# 23_LMS2_RX1_BB_ADC.net
KiCad netlist of a schematic drawn in Altium Designer
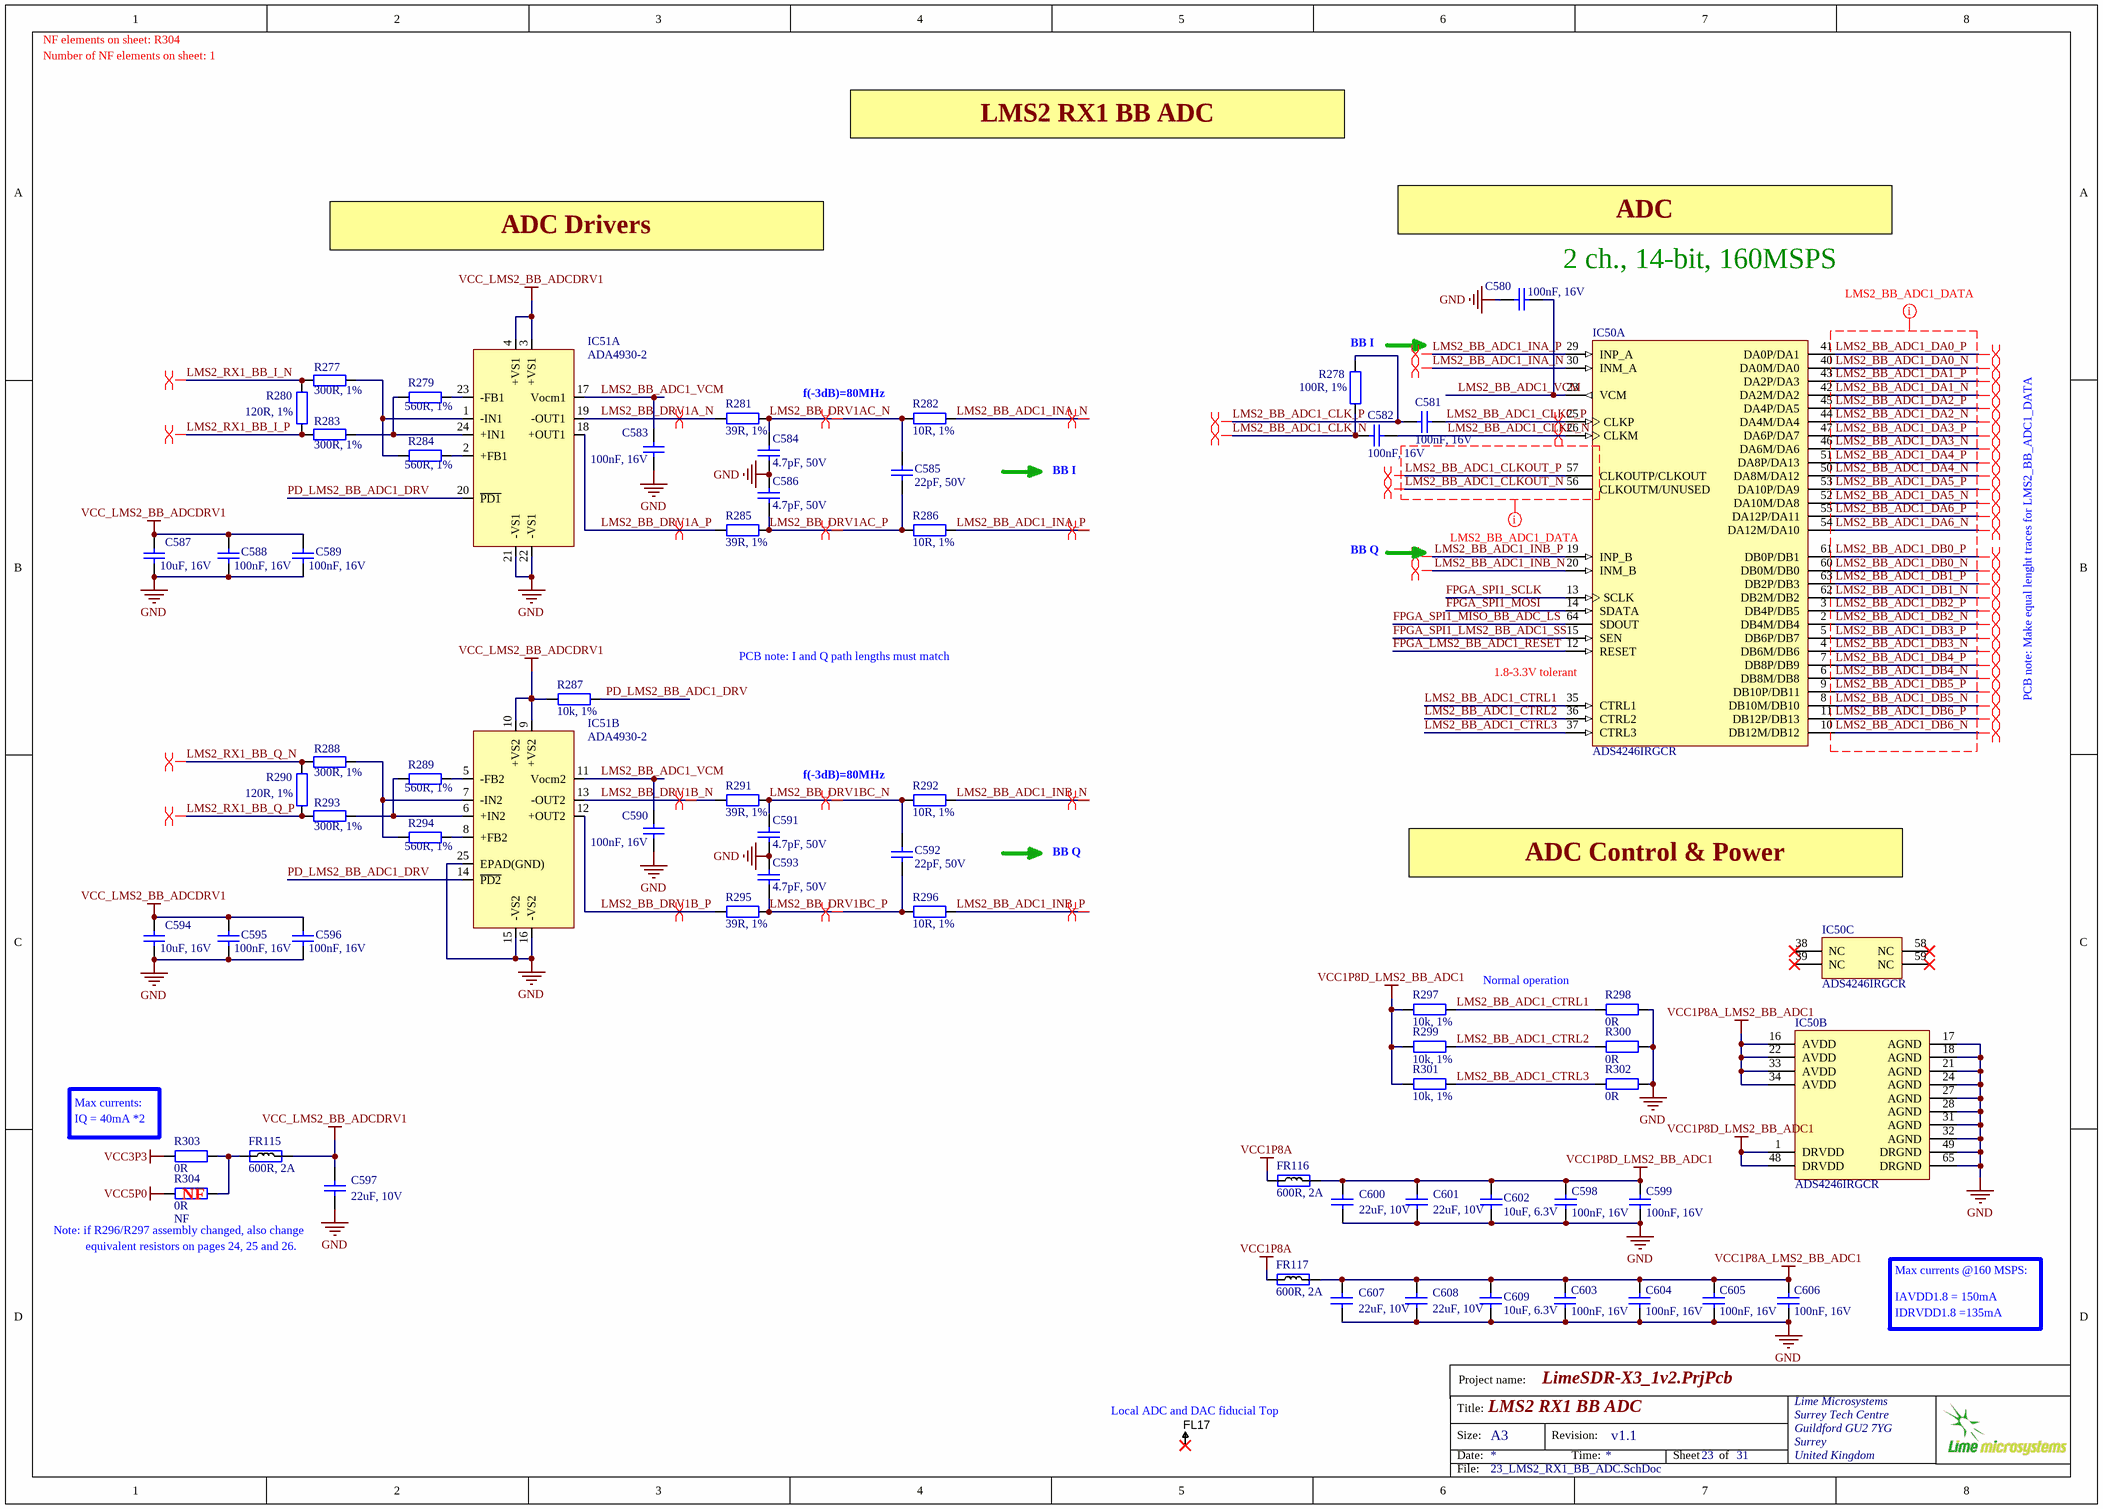
[diagram p0: 23_LMS2_RX1_BB_ADC.SchDoc]

(export (version "E")
  (design (tool "Eeschema 10.0.6"))
  (components
    (comp (ref "C580")
      (value "100nF, 16V")
      (footprint "CAP0402")
      (fields (field (name "TOLERANCE") "10 %") (field (name "MANUFACTURER") "Murata Electronics"))
      (libsource (lib "") (part "Cap_0603_2"))
    )
    (comp (ref "C581")
      (value "100nF, 16V")
      (footprint "CAP0402")
      (fields (field (name "TOLERANCE") "10 %") (field (name "MANUFACTURER") "Murata Electronics"))
      (libsource (lib "") (part "Cap_0603_2"))
    )
    (comp (ref "C582")
      (value "100nF, 16V")
      (footprint "CAP0402")
      (fields (field (name "TOLERANCE") "10 %") (field (name "MANUFACTURER") "Murata Electronics"))
      (libsource (lib "") (part "Cap_0603_5"))
    )
    (comp (ref "C583")
      (value "100nF, 16V")
      (footprint "CAP0402")
      (fields (field (name "TOLERANCE") "10 %") (field (name "MANUFACTURER") "Murata Electronics"))
      (libsource (lib "") (part "Cap_0603_5"))
    )
    (comp (ref "C584")
      (value "4.7pF, 50V")
      (footprint "CAP0402")
      (fields (field (name "MANUFACTURER") "MURATA"))
      (libsource (lib "LimeMicroAltiumLib_schLib") (part "Cap_0402"))
    )
    (comp (ref "C585")
      (value "22pF, 50V")
      (footprint "CAP0402")
      (fields (field (name "TOLERANCE") "±5%") (field (name "MANUFACTURER") "Yageo"))
      (libsource (lib "") (part "Cap_0402_1"))
    )
    (comp (ref "C586")
      (value "4.7pF, 50V")
      (footprint "CAP0402")
      (fields (field (name "MANUFACTURER") "MURATA"))
      (libsource (lib "LimeMicroAltiumLib_schLib") (part "Cap_0402"))
    )
    (comp (ref "C587")
      (value "10uF, 16V")
      (footprint "CAP0603")
      (fields (field (name "MANUFACTURER") "Yageo") (field (name "TOLERANCE") "±20%"))
      (libsource (lib "LimeMicroAltiumLib_schLib") (part "Cap_0603"))
    )
    (comp (ref "C588")
      (value "100nF, 16V")
      (footprint "CAP0402")
      (fields (field (name "TOLERANCE") "10 %") (field (name "MANUFACTURER") "Murata Electronics"))
      (libsource (lib "") (part "Cap_0603_5"))
    )
    (comp (ref "C589")
      (value "100nF, 16V")
      (footprint "CAP0402")
      (fields (field (name "TOLERANCE") "10 %") (field (name "MANUFACTURER") "Murata Electronics"))
      (libsource (lib "") (part "Cap_0603_5"))
    )
    (comp (ref "C590")
      (value "100nF, 16V")
      (footprint "CAP0402")
      (fields (field (name "TOLERANCE") "10 %") (field (name "MANUFACTURER") "Murata Electronics"))
      (libsource (lib "") (part "Cap_0603_7"))
    )
    (comp (ref "C591")
      (value "4.7pF, 50V")
      (footprint "CAP0402")
      (fields (field (name "MANUFACTURER") "MURATA"))
      (libsource (lib "LimeMicroAltiumLib_schLib") (part "Cap_0402"))
    )
    (comp (ref "C592")
      (value "22pF, 50V")
      (footprint "CAP0402")
      (fields (field (name "TOLERANCE") "±5%") (field (name "MANUFACTURER") "Yageo"))
      (libsource (lib "") (part "Cap_0402_1"))
    )
    (comp (ref "C593")
      (value "4.7pF, 50V")
      (footprint "CAP0402")
      (fields (field (name "MANUFACTURER") "MURATA"))
      (libsource (lib "LimeMicroAltiumLib_schLib") (part "Cap_0402"))
    )
    (comp (ref "C594")
      (value "10uF, 16V")
      (footprint "CAP0603")
      (fields (field (name "MANUFACTURER") "Yageo") (field (name "TOLERANCE") "±20%"))
      (libsource (lib "LimeMicroAltiumLib_schLib") (part "Cap_0603"))
    )
    (comp (ref "C595")
      (value "100nF, 16V")
      (footprint "CAP0402")
      (fields (field (name "TOLERANCE") "10 %") (field (name "MANUFACTURER") "Murata Electronics"))
      (libsource (lib "") (part "Cap_0603_5"))
    )
    (comp (ref "C596")
      (value "100nF, 16V")
      (footprint "CAP0402")
      (fields (field (name "TOLERANCE") "10 %") (field (name "MANUFACTURER") "Murata Electronics"))
      (libsource (lib "") (part "Cap_0603_5"))
    )
    (comp (ref "C597")
      (value "22uF, 10V")
      (footprint "CAP0603")
      (fields (field (name "TOLERANCE") "20 %") (field (name "MANUFACTURER") "TDK Corporation"))
      (libsource (lib "") (part "Cap_0603_4"))
    )
    (comp (ref "C598")
      (value "100nF, 16V")
      (footprint "CAP0402")
      (fields (field (name "TOLERANCE") "10 %") (field (name "MANUFACTURER") "Murata Electronics"))
      (libsource (lib "LimeFPGAboard_schLib") (part "Cap_0603"))
    )
    (comp (ref "C599")
      (value "100nF, 16V")
      (footprint "CAP0402")
      (fields (field (name "TOLERANCE") "10 %") (field (name "MANUFACTURER") "Murata Electronics"))
      (libsource (lib "LimeFPGAboard_schLib") (part "Cap_0603"))
    )
    (comp (ref "C600")
      (value "22uF, 10V")
      (footprint "CAP0603")
      (fields (field (name "TOLERANCE") "20 %") (field (name "MANUFACTURER") "TDK Corporation"))
      (libsource (lib "LimeFPGAboard_schLib") (part "Cap_0603"))
    )
    (comp (ref "C601")
      (value "22uF, 10V")
      (footprint "CAP0603")
      (fields (field (name "TOLERANCE") "20 %") (field (name "MANUFACTURER") "TDK Corporation"))
      (libsource (lib "LimeFPGAboard_schLib") (part "Cap_0603"))
    )
    (comp (ref "C602")
      (value "10uF, 6.3V")
      (footprint "CAP0603")
      (fields (field (name "TOLERANCE") "±20%") (field (name "MANUFACTURER") "Yageo"))
      (libsource (lib "") (part "Cap_0603_6"))
    )
    (comp (ref "C603")
      (value "100nF, 16V")
      (footprint "CAP0402")
      (fields (field (name "TOLERANCE") "10 %") (field (name "MANUFACTURER") "Murata Electronics"))
      (libsource (lib "") (part "Cap_0603_3"))
    )
    (comp (ref "C604")
      (value "100nF, 16V")
      (footprint "CAP0402")
      (fields (field (name "TOLERANCE") "10 %") (field (name "MANUFACTURER") "Murata Electronics"))
      (libsource (lib "") (part "Cap_0603_3"))
    )
    (comp (ref "C605")
      (value "100nF, 16V")
      (footprint "CAP0402")
      (fields (field (name "TOLERANCE") "10 %") (field (name "MANUFACTURER") "Murata Electronics"))
      (libsource (lib "") (part "Cap_0603_3"))
    )
    (comp (ref "C606")
      (value "100nF, 16V")
      (footprint "CAP0402")
      (fields (field (name "TOLERANCE") "10 %") (field (name "MANUFACTURER") "Murata Electronics"))
      (libsource (lib "") (part "Cap_0603_3"))
    )
    (comp (ref "C607")
      (value "22uF, 10V")
      (footprint "CAP0603")
      (fields (field (name "TOLERANCE") "20 %") (field (name "MANUFACTURER") "TDK Corporation"))
      (libsource (lib "") (part "Cap_0603_3"))
    )
    (comp (ref "C608")
      (value "22uF, 10V")
      (footprint "CAP0603")
      (fields (field (name "TOLERANCE") "20 %") (field (name "MANUFACTURER") "TDK Corporation"))
      (libsource (lib "") (part "Cap_0603_3"))
    )
    (comp (ref "C609")
      (value "10uF, 6.3V")
      (footprint "CAP0603")
      (fields (field (name "TOLERANCE") "±20%") (field (name "MANUFACTURER") "Yageo"))
      (libsource (lib "") (part "Cap_0603_1"))
    )
    (comp (ref "FL17")
      (value "Fiducial")
      (footprint "Fiducial_local")
      (libsource (lib "LimeMicroAltiumLib_schLib") (part "Fiducial"))
    )
    (comp (ref "FR115")
      (value "600R, 2A")
      (footprint "RES0805")
      (fields (field (name "MANUFACTURER") "TDK Corporation"))
      (libsource (lib "LimeMicroAltiumLib_schLib") (part "Ferrite"))
    )
    (comp (ref "FR116")
      (value "600R, 2A")
      (footprint "RES0805")
      (fields (field (name "MANUFACTURER") "TDK Corporation"))
      (libsource (lib "LimeFPGAboard_schLib") (part "Ferrite"))
    )
    (comp (ref "FR117")
      (value "600R, 2A")
      (footprint "RES0805")
      (fields (field (name "MANUFACTURER") "TDK Corporation"))
      (libsource (lib "LimeFPGAboard_schLib") (part "Ferrite"))
    )
    (comp (ref "IC50")
      (value "ADS4246IRGCR")
      (footprint "TI-RGC64-7400X7400TP_V")
      (description "14-Bit 160 MSPS Dual Low Power ADC, -40 to 85 degC, 64-pin QFN (RGC64), Green (RoHS & no Sb/Br)")
      (fields (field (name "MANUFACTURER") "Texas Instruments"))
      (libsource (lib "LimeMicroAltiumLib_schLib") (part "ADS4246IRGCR"))
    )
    (comp (ref "IC51")
      (value "ADA4930-2")
      (footprint "ADA4930-2_LFCSP-24")
      (fields (field (name "MANUFACTURER") "Analog Devices Inc."))
      (libsource (lib "LimeMicroAltiumLib_schLib") (part "ADA4930-2"))
    )
    (comp (ref "R277")
      (value "300R, 1%")
      (footprint "RES0402")
      (fields (field (name "TOLERANCE") "±1%") (field (name "MANUFACTURER") "Vishay Dale"))
      (libsource (lib "LimeFPGAboard_schLib") (part "Res_0402"))
    )
    (comp (ref "R278")
      (value "100R, 1%")
      (footprint "RES0402")
      (fields (field (name "TOLERANCE") "±1%") (field (name "MANUFACTURER") "Stackpole Electronics Inc."))
      (libsource (lib "LimeFPGAboard_schLib") (part "Res_0402"))
    )
    (comp (ref "R279")
      (value "560R, 1%")
      (footprint "RES0402")
      (fields (field (name "TOLERANCE") "±1%") (field (name "MANUFACTURER") "Vishay Dale"))
      (libsource (lib "LimeFPGAboard_schLib") (part "Res_0402"))
    )
    (comp (ref "R280")
      (value "120R, 1%")
      (footprint "RES0402")
      (fields (field (name "MANUFACTURER") "Yageo") (field (name "TOLERANCE") "1%"))
      (libsource (lib "") (part "Res_0402_1"))
    )
    (comp (ref "R281")
      (value "39R, 1%")
      (footprint "RES0402")
      (fields (field (name "MANUFACTURER") "Yageo") (field (name "TOLERANCE") "1%"))
      (libsource (lib "LimeMicroAltiumLib_schLib") (part "Res_0402"))
    )
    (comp (ref "R282")
      (value "10R, 1%")
      (footprint "RES0402")
      (fields (field (name "TOLERANCE") "1%"))
      (libsource (lib "LimeMicroAltiumLib_schLib") (part "Res_0402"))
    )
    (comp (ref "R283")
      (value "300R, 1%")
      (footprint "RES0402")
      (fields (field (name "TOLERANCE") "±1%") (field (name "MANUFACTURER") "Vishay Dale"))
      (libsource (lib "LimeFPGAboard_schLib") (part "Res_0402"))
    )
    (comp (ref "R284")
      (value "560R, 1%")
      (footprint "RES0402")
      (fields (field (name "TOLERANCE") "±1%") (field (name "MANUFACTURER") "Vishay Dale"))
      (libsource (lib "LimeFPGAboard_schLib") (part "Res_0402"))
    )
    (comp (ref "R285")
      (value "39R, 1%")
      (footprint "RES0402")
      (fields (field (name "MANUFACTURER") "Yageo") (field (name "TOLERANCE") "1%"))
      (libsource (lib "LimeMicroAltiumLib_schLib") (part "Res_0402"))
    )
    (comp (ref "R286")
      (value "10R, 1%")
      (footprint "RES0402")
      (fields (field (name "TOLERANCE") "1%"))
      (libsource (lib "LimeMicroAltiumLib_schLib") (part "Res_0402"))
    )
    (comp (ref "R287")
      (value "10k, 1%")
      (footprint "RES0402")
      (fields (field (name "MANUFACTURER") "Yageo") (field (name "TOLERANCE") "±1%"))
      (libsource (lib "LimeMicroAltiumLib_schLib") (part "Res_0402"))
    )
    (comp (ref "R288")
      (value "300R, 1%")
      (footprint "RES0402")
      (fields (field (name "TOLERANCE") "±1%") (field (name "MANUFACTURER") "Vishay Dale"))
      (libsource (lib "LimeFPGAboard_schLib") (part "Res_0402"))
    )
    (comp (ref "R289")
      (value "560R, 1%")
      (footprint "RES0402")
      (fields (field (name "TOLERANCE") "±1%") (field (name "MANUFACTURER") "Vishay Dale"))
      (libsource (lib "LimeFPGAboard_schLib") (part "Res_0402"))
    )
    (comp (ref "R290")
      (value "120R, 1%")
      (footprint "RES0402")
      (fields (field (name "MANUFACTURER") "Yageo") (field (name "TOLERANCE") "1%"))
      (libsource (lib "") (part "Res_0402_1"))
    )
    (comp (ref "R291")
      (value "39R, 1%")
      (footprint "RES0402")
      (fields (field (name "MANUFACTURER") "Yageo") (field (name "TOLERANCE") "1%"))
      (libsource (lib "LimeMicroAltiumLib_schLib") (part "Res_0402"))
    )
    (comp (ref "R292")
      (value "10R, 1%")
      (footprint "RES0402")
      (fields (field (name "TOLERANCE") "1%"))
      (libsource (lib "LimeMicroAltiumLib_schLib") (part "Res_0402"))
    )
    (comp (ref "R293")
      (value "300R, 1%")
      (footprint "RES0402")
      (fields (field (name "TOLERANCE") "±1%") (field (name "MANUFACTURER") "Vishay Dale"))
      (libsource (lib "LimeFPGAboard_schLib") (part "Res_0402"))
    )
    (comp (ref "R294")
      (value "560R, 1%")
      (footprint "RES0402")
      (fields (field (name "TOLERANCE") "±1%") (field (name "MANUFACTURER") "Vishay Dale"))
      (libsource (lib "LimeFPGAboard_schLib") (part "Res_0402"))
    )
    (comp (ref "R295")
      (value "39R, 1%")
      (footprint "RES0402")
      (fields (field (name "MANUFACTURER") "Yageo") (field (name "TOLERANCE") "1%"))
      (libsource (lib "LimeMicroAltiumLib_schLib") (part "Res_0402"))
    )
    (comp (ref "R296")
      (value "10R, 1%")
      (footprint "RES0402")
      (fields (field (name "TOLERANCE") "1%"))
      (libsource (lib "LimeMicroAltiumLib_schLib") (part "Res_0402"))
    )
    (comp (ref "R297")
      (value "10k, 1%")
      (footprint "RES0402")
      (fields (field (name "MANUFACTURER") "Yageo") (field (name "TOLERANCE") "±1%"))
      (libsource (lib "LimeMicroAltiumLib_schLib") (part "Res_0402"))
    )
    (comp (ref "R298")
      (value "0R")
      (footprint "RES0402")
      (fields (field (name "MANUFACTURER") "Yageo"))
      (libsource (lib "LimeFPGAboard_schLib") (part "Res_0402"))
    )
    (comp (ref "R299")
      (value "10k, 1%")
      (footprint "RES0402")
      (fields (field (name "MANUFACTURER") "Yageo") (field (name "TOLERANCE") "±1%"))
      (libsource (lib "LimeMicroAltiumLib_schLib") (part "Res_0402"))
    )
    (comp (ref "R300")
      (value "0R")
      (footprint "RES0402")
      (fields (field (name "MANUFACTURER") "Yageo"))
      (libsource (lib "LimeFPGAboard_schLib") (part "Res_0402"))
    )
    (comp (ref "R301")
      (value "10k, 1%")
      (footprint "RES0402")
      (fields (field (name "MANUFACTURER") "Yageo") (field (name "TOLERANCE") "±1%"))
      (libsource (lib "LimeMicroAltiumLib_schLib") (part "Res_0402"))
    )
    (comp (ref "R302")
      (value "0R")
      (footprint "RES0402")
      (fields (field (name "MANUFACTURER") "Yageo"))
      (libsource (lib "LimeFPGAboard_schLib") (part "Res_0402"))
    )
    (comp (ref "R303")
      (value "0R")
      (footprint "RES0402")
      (fields (field (name "MANUFACTURER") "Yageo") (field (name "TOLERANCE") "Jumper"))
      (libsource (lib "LimeMicroAltiumLib_schLib") (part "Res_0402"))
    )
    (comp (ref "R304")
      (value "0R")
      (footprint "RES0402")
      (fields
        (field (name "ASSEMBLY INFO") "NF")
        (field (name "MANUFACTURER") "Yageo")
        (field (name "TOLERANCE") "Jumper")
      )
      (libsource (lib "LimeMicroAltiumLib_schLib") (part "Res_0402"))
    )
  )
  (nets
    (net (code "1") (name "/FPGA_LMS2_BB_ADC1_RESET") (class "Default")
      (node (ref "IC50") (pin "12") (pinfunction "RESET_12") (pintype "input"))
    )
    (net (code "2") (name "/FPGA_SPI1_LMS2_BB_ADC1_SS") (class "Default")
      (node (ref "IC50") (pin "15") (pinfunction "SEN_15") (pintype "input"))
    )
    (net (code "3") (name "/FPGA_SPI1_MISO_BB_ADC_LS") (class "Default")
      (node (ref "IC50") (pin "64") (pinfunction "SDOUT_64") (pintype "tri_state"))
    )
    (net (code "4") (name "/FPGA_SPI1_MOSI") (class "Default")
      (node (ref "IC50") (pin "14") (pinfunction "SDATA_14") (pintype "input"))
    )
    (net (code "5") (name "/FPGA_SPI1_SCLK") (class "Default")
      (node (ref "IC50") (pin "13") (pinfunction "SCLK_13") (pintype "input"))
    )
    (net (code "6") (name "/LMS2_BB_ADC1_CLKC_N") (class "Default")
      (node (ref "C582") (pin "1") (pinfunction "1_1") (pintype "passive"))
      (node (ref "IC50") (pin "26") (pinfunction "CLKM_26") (pintype "input"))
    )
    (net (code "7") (name "/LMS2_BB_ADC1_CLKC_P") (class "Default")
      (node (ref "C581") (pin "1") (pinfunction "1_1") (pintype "passive"))
      (node (ref "IC50") (pin "25") (pinfunction "CLKP_25") (pintype "input"))
    )
    (net (code "8") (name "/LMS2_BB_ADC1_CLKOUT_N") (class "Default")
      (node (ref "IC50") (pin "56") (pinfunction "CLKOUTM/UNUSED_56") (pintype "tri_state"))
    )
    (net (code "9") (name "/LMS2_BB_ADC1_CLKOUT_P") (class "Default")
      (node (ref "IC50") (pin "57") (pinfunction "CLKOUTP/CLKOUT_57") (pintype "tri_state"))
    )
    (net (code "10") (name "/LMS2_BB_ADC1_CLK_N") (class "Default")
      (node (ref "C582") (pin "2") (pinfunction "2_2") (pintype "passive"))
      (node (ref "R278") (pin "1") (pinfunction "1_1") (pintype "passive"))
    )
    (net (code "11") (name "/LMS2_BB_ADC1_CLK_P") (class "Default")
      (node (ref "C581") (pin "2") (pinfunction "2_2") (pintype "passive"))
      (node (ref "R278") (pin "2") (pinfunction "2_2") (pintype "passive"))
    )
    (net (code "12") (name "/LMS2_BB_ADC1_CTRL1") (class "Default")
      (node (ref "IC50") (pin "35") (pinfunction "CTRL1_35") (pintype "input"))
      (node (ref "R297") (pin "1") (pinfunction "1_1") (pintype "passive"))
      (node (ref "R298") (pin "2") (pinfunction "2_2") (pintype "passive"))
    )
    (net (code "13") (name "/LMS2_BB_ADC1_CTRL2") (class "Default")
      (node (ref "IC50") (pin "36") (pinfunction "CTRL2_36") (pintype "input"))
      (node (ref "R299") (pin "1") (pinfunction "1_1") (pintype "passive"))
      (node (ref "R300") (pin "2") (pinfunction "2_2") (pintype "passive"))
    )
    (net (code "14") (name "/LMS2_BB_ADC1_CTRL3") (class "Default")
      (node (ref "IC50") (pin "37") (pinfunction "CTRL3_37") (pintype "input"))
      (node (ref "R301") (pin "1") (pinfunction "1_1") (pintype "passive"))
      (node (ref "R302") (pin "2") (pinfunction "2_2") (pintype "passive"))
    )
    (net (code "15") (name "/LMS2_BB_ADC1_DA0_N") (class "Default")
      (node (ref "IC50") (pin "40") (pinfunction "DA0M/DA0_40") (pintype "tri_state"))
    )
    (net (code "16") (name "/LMS2_BB_ADC1_DA0_P") (class "Default")
      (node (ref "IC50") (pin "41") (pinfunction "DA0P/DA1_41") (pintype "tri_state"))
    )
    (net (code "17") (name "/LMS2_BB_ADC1_DA1_N") (class "Default")
      (node (ref "IC50") (pin "42") (pinfunction "DA2M/DA2_42") (pintype "tri_state"))
    )
    (net (code "18") (name "/LMS2_BB_ADC1_DA1_P") (class "Default")
      (node (ref "IC50") (pin "43") (pinfunction "DA2P/DA3_43") (pintype "tri_state"))
    )
    (net (code "19") (name "/LMS2_BB_ADC1_DA2_N") (class "Default")
      (node (ref "IC50") (pin "44") (pinfunction "DA4M/DA4_44") (pintype "tri_state"))
    )
    (net (code "20") (name "/LMS2_BB_ADC1_DA2_P") (class "Default")
      (node (ref "IC50") (pin "45") (pinfunction "DA4P/DA5_45") (pintype "tri_state"))
    )
    (net (code "21") (name "/LMS2_BB_ADC1_DA3_N") (class "Default")
      (node (ref "IC50") (pin "46") (pinfunction "DA6M/DA6_46") (pintype "tri_state"))
    )
    (net (code "22") (name "/LMS2_BB_ADC1_DA3_P") (class "Default")
      (node (ref "IC50") (pin "47") (pinfunction "DA6P/DA7_47") (pintype "tri_state"))
    )
    (net (code "23") (name "/LMS2_BB_ADC1_DA4_N") (class "Default")
      (node (ref "IC50") (pin "50") (pinfunction "DA8M/DA12_50") (pintype "tri_state"))
    )
    (net (code "24") (name "/LMS2_BB_ADC1_DA4_P") (class "Default")
      (node (ref "IC50") (pin "51") (pinfunction "DA8P/DA13_51") (pintype "tri_state"))
    )
    (net (code "25") (name "/LMS2_BB_ADC1_DA5_N") (class "Default")
      (node (ref "IC50") (pin "52") (pinfunction "DA10M/DA8_52") (pintype "tri_state"))
    )
    (net (code "26") (name "/LMS2_BB_ADC1_DA5_P") (class "Default")
      (node (ref "IC50") (pin "53") (pinfunction "DA10P/DA9_53") (pintype "tri_state"))
    )
    (net (code "27") (name "/LMS2_BB_ADC1_DA6_N") (class "Default")
      (node (ref "IC50") (pin "54") (pinfunction "DA12M/DA10_54") (pintype "tri_state"))
    )
    (net (code "28") (name "/LMS2_BB_ADC1_DA6_P") (class "Default")
      (node (ref "IC50") (pin "55") (pinfunction "DA12P/DA11_55") (pintype "tri_state"))
    )
    (net (code "29") (name "/LMS2_BB_ADC1_DB0_N") (class "Default")
      (node (ref "IC50") (pin "60") (pinfunction "DB0M/DB0_60") (pintype "tri_state"))
    )
    (net (code "30") (name "/LMS2_BB_ADC1_DB0_P") (class "Default")
      (node (ref "IC50") (pin "61") (pinfunction "DB0P/DB1_61") (pintype "tri_state"))
    )
    (net (code "31") (name "/LMS2_BB_ADC1_DB1_N") (class "Default")
      (node (ref "IC50") (pin "62") (pinfunction "DB2M/DB2_62") (pintype "tri_state"))
    )
    (net (code "32") (name "/LMS2_BB_ADC1_DB1_P") (class "Default")
      (node (ref "IC50") (pin "63") (pinfunction "DB2P/DB3_63") (pintype "tri_state"))
    )
    (net (code "33") (name "/LMS2_BB_ADC1_DB2_N") (class "Default")
      (node (ref "IC50") (pin "2") (pinfunction "DB4M/DB4_2") (pintype "tri_state"))
    )
    (net (code "34") (name "/LMS2_BB_ADC1_DB2_P") (class "Default")
      (node (ref "IC50") (pin "3") (pinfunction "DB4P/DB5_3") (pintype "tri_state"))
    )
    (net (code "35") (name "/LMS2_BB_ADC1_DB3_N") (class "Default")
      (node (ref "IC50") (pin "4") (pinfunction "DB6M/DB6_4") (pintype "tri_state"))
    )
    (net (code "36") (name "/LMS2_BB_ADC1_DB3_P") (class "Default")
      (node (ref "IC50") (pin "5") (pinfunction "DB6P/DB7_5") (pintype "tri_state"))
    )
    (net (code "37") (name "/LMS2_BB_ADC1_DB4_N") (class "Default")
      (node (ref "IC50") (pin "6") (pinfunction "DB8M/DB8_6") (pintype "tri_state"))
    )
    (net (code "38") (name "/LMS2_BB_ADC1_DB4_P") (class "Default")
      (node (ref "IC50") (pin "7") (pinfunction "DB8P/DB9_7") (pintype "tri_state"))
    )
    (net (code "39") (name "/LMS2_BB_ADC1_DB5_N") (class "Default")
      (node (ref "IC50") (pin "8") (pinfunction "DB10M/DB10_8") (pintype "tri_state"))
    )
    (net (code "40") (name "/LMS2_BB_ADC1_DB5_P") (class "Default")
      (node (ref "IC50") (pin "9") (pinfunction "DB10P/DB11_9") (pintype "tri_state"))
    )
    (net (code "41") (name "/LMS2_BB_ADC1_DB6_N") (class "Default")
      (node (ref "IC50") (pin "10") (pinfunction "DB12M/DB12_10") (pintype "tri_state"))
    )
    (net (code "42") (name "/LMS2_BB_ADC1_DB6_P") (class "Default")
      (node (ref "IC50") (pin "11") (pinfunction "DB12P/DB13_11") (pintype "tri_state"))
    )
    (net (code "43") (name "/LMS2_BB_ADC1_INA_N") (class "Default")
      (node (ref "IC50") (pin "30") (pinfunction "INM_A_30") (pintype "input"))
      (node (ref "R282") (pin "1") (pinfunction "1_1") (pintype "passive"))
    )
    (net (code "44") (name "/LMS2_BB_ADC1_INA_P") (class "Default")
      (node (ref "IC50") (pin "29") (pinfunction "INP_A_29") (pintype "input"))
      (node (ref "R286") (pin "1") (pinfunction "1_1") (pintype "passive"))
    )
    (net (code "45") (name "/LMS2_BB_ADC1_INB_N") (class "Default")
      (node (ref "IC50") (pin "20") (pinfunction "INM_B_20") (pintype "input"))
      (node (ref "R292") (pin "1") (pinfunction "1_1") (pintype "passive"))
    )
    (net (code "46") (name "/LMS2_BB_ADC1_INB_P") (class "Default")
      (node (ref "IC50") (pin "19") (pinfunction "INP_B_19") (pintype "input"))
      (node (ref "R296") (pin "1") (pinfunction "1_1") (pintype "passive"))
    )
    (net (code "47") (name "/LMS2_BB_ADC1_VCM") (class "Default")
      (node (ref "C580") (pin "2") (pinfunction "2_2") (pintype "passive"))
      (node (ref "C583") (pin "1") (pinfunction "1_1") (pintype "passive"))
      (node (ref "C590") (pin "1") (pinfunction "1_1") (pintype "passive"))
      (node (ref "IC50") (pin "23") (pinfunction "VCM_23") (pintype "output"))
      (node (ref "IC51") (pin "11") (pinfunction "Vocm2_11") (pintype "input"))
      (node (ref "IC51") (pin "17") (pinfunction "Vocm1_17") (pintype "input"))
    )
    (net (code "48") (name "/LMS2_BB_DRV1AC_N") (class "Default")
      (node (ref "C584") (pin "1") (pinfunction "1_1") (pintype "passive"))
      (node (ref "C585") (pin "1") (pinfunction "1_1") (pintype "passive"))
      (node (ref "R281") (pin "1") (pinfunction "1_1") (pintype "passive"))
      (node (ref "R282") (pin "2") (pinfunction "2_2") (pintype "passive"))
    )
    (net (code "49") (name "/LMS2_BB_DRV1AC_P") (class "Default")
      (node (ref "C585") (pin "2") (pinfunction "2_2") (pintype "passive"))
      (node (ref "C586") (pin "2") (pinfunction "2_2") (pintype "passive"))
      (node (ref "R285") (pin "1") (pinfunction "1_1") (pintype "passive"))
      (node (ref "R286") (pin "2") (pinfunction "2_2") (pintype "passive"))
    )
    (net (code "50") (name "/LMS2_BB_DRV1A_N") (class "Default")
      (node (ref "IC51") (pin "19") (pinfunction "-OUT1_19") (pintype "output"))
      (node (ref "R281") (pin "2") (pinfunction "2_2") (pintype "passive"))
    )
    (net (code "51") (name "/LMS2_BB_DRV1A_P") (class "Default")
      (node (ref "IC51") (pin "18") (pinfunction "+OUT1_18") (pintype "output"))
      (node (ref "R285") (pin "2") (pinfunction "2_2") (pintype "passive"))
    )
    (net (code "52") (name "/LMS2_BB_DRV1BC_N") (class "Default")
      (node (ref "C591") (pin "1") (pinfunction "1_1") (pintype "passive"))
      (node (ref "C592") (pin "1") (pinfunction "1_1") (pintype "passive"))
      (node (ref "R291") (pin "1") (pinfunction "1_1") (pintype "passive"))
      (node (ref "R292") (pin "2") (pinfunction "2_2") (pintype "passive"))
    )
    (net (code "53") (name "/LMS2_BB_DRV1BC_P") (class "Default")
      (node (ref "C592") (pin "2") (pinfunction "2_2") (pintype "passive"))
      (node (ref "C593") (pin "2") (pinfunction "2_2") (pintype "passive"))
      (node (ref "R295") (pin "1") (pinfunction "1_1") (pintype "passive"))
      (node (ref "R296") (pin "2") (pinfunction "2_2") (pintype "passive"))
    )
    (net (code "54") (name "/LMS2_BB_DRV1B_N") (class "Default")
      (node (ref "IC51") (pin "13") (pinfunction "-OUT2_13") (pintype "output"))
      (node (ref "R291") (pin "2") (pinfunction "2_2") (pintype "passive"))
    )
    (net (code "55") (name "/LMS2_BB_DRV1B_P") (class "Default")
      (node (ref "IC51") (pin "12") (pinfunction "+OUT2_12") (pintype "output"))
      (node (ref "R295") (pin "2") (pinfunction "2_2") (pintype "passive"))
    )
    (net (code "56") (name "/LMS2_RX1_BB_I_N") (class "Default")
      (node (ref "R277") (pin "2") (pinfunction "2_2") (pintype "passive"))
      (node (ref "R280") (pin "2") (pinfunction "2_2") (pintype "passive"))
    )
    (net (code "57") (name "/LMS2_RX1_BB_I_P") (class "Default")
      (node (ref "R280") (pin "1") (pinfunction "1_1") (pintype "passive"))
      (node (ref "R283") (pin "2") (pinfunction "2_2") (pintype "passive"))
    )
    (net (code "58") (name "/LMS2_RX1_BB_Q_N") (class "Default")
      (node (ref "R288") (pin "2") (pinfunction "2_2") (pintype "passive"))
      (node (ref "R290") (pin "2") (pinfunction "2_2") (pintype "passive"))
    )
    (net (code "59") (name "/LMS2_RX1_BB_Q_P") (class "Default")
      (node (ref "R290") (pin "1") (pinfunction "1_1") (pintype "passive"))
      (node (ref "R293") (pin "2") (pinfunction "2_2") (pintype "passive"))
    )
    (net (code "60") (name "/PD_LMS2_BB_ADC1_DRV") (class "Default")
      (node (ref "IC51") (pin "14") (pinfunction "~{PD2}_14") (pintype "input"))
      (node (ref "IC51") (pin "20") (pinfunction "~{PD1}_20") (pintype "input"))
      (node (ref "R287") (pin "1") (pinfunction "1_1") (pintype "passive"))
    )
    (net (code "61") (name "GND") (class "Default")
      (node (ref "C580") (pin "1") (pinfunction "1_1") (pintype "passive"))
      (node (ref "C583") (pin "2") (pinfunction "2_2") (pintype "passive"))
      (node (ref "C584") (pin "2") (pinfunction "2_2") (pintype "passive"))
      (node (ref "C586") (pin "1") (pinfunction "1_1") (pintype "passive"))
      (node (ref "C587") (pin "1") (pinfunction "1_1") (pintype "passive"))
      (node (ref "C588") (pin "2") (pinfunction "2_2") (pintype "passive"))
      (node (ref "C589") (pin "2") (pinfunction "2_2") (pintype "passive"))
      (node (ref "C590") (pin "2") (pinfunction "2_2") (pintype "passive"))
      (node (ref "C591") (pin "2") (pinfunction "2_2") (pintype "passive"))
      (node (ref "C593") (pin "1") (pinfunction "1_1") (pintype "passive"))
      (node (ref "C594") (pin "1") (pinfunction "1_1") (pintype "passive"))
      (node (ref "C595") (pin "2") (pinfunction "2_2") (pintype "passive"))
      (node (ref "C596") (pin "2") (pinfunction "2_2") (pintype "passive"))
      (node (ref "C597") (pin "1") (pinfunction "1_1") (pintype "passive"))
      (node (ref "C598") (pin "1") (pinfunction "1_1") (pintype "passive"))
      (node (ref "C599") (pin "1") (pinfunction "1_1") (pintype "passive"))
      (node (ref "C600") (pin "1") (pinfunction "1_1") (pintype "passive"))
      (node (ref "C601") (pin "1") (pinfunction "1_1") (pintype "passive"))
      (node (ref "C602") (pin "2") (pinfunction "2_2") (pintype "passive"))
      (node (ref "C603") (pin "1") (pinfunction "1_1") (pintype "passive"))
      (node (ref "C604") (pin "1") (pinfunction "1_1") (pintype "passive"))
      (node (ref "C605") (pin "1") (pinfunction "1_1") (pintype "passive"))
      (node (ref "C606") (pin "1") (pinfunction "1_1") (pintype "passive"))
      (node (ref "C607") (pin "1") (pinfunction "1_1") (pintype "passive"))
      (node (ref "C608") (pin "1") (pinfunction "1_1") (pintype "passive"))
      (node (ref "C609") (pin "2") (pinfunction "2_2") (pintype "passive"))
      (node (ref "IC50") (pin "17") (pinfunction "AGND_17") (pintype "power_in"))
      (node (ref "IC50") (pin "18") (pinfunction "AGND_18") (pintype "power_in"))
      (node (ref "IC50") (pin "21") (pinfunction "AGND_21") (pintype "power_in"))
      (node (ref "IC50") (pin "24") (pinfunction "AGND_24") (pintype "power_in"))
      (node (ref "IC50") (pin "27") (pinfunction "AGND_27") (pintype "power_in"))
      (node (ref "IC50") (pin "28") (pinfunction "AGND_28") (pintype "power_in"))
      (node (ref "IC50") (pin "31") (pinfunction "AGND_31") (pintype "power_in"))
      (node (ref "IC50") (pin "32") (pinfunction "AGND_32") (pintype "power_in"))
      (node (ref "IC50") (pin "49") (pinfunction "DRGND_49") (pintype "power_in"))
      (node (ref "IC50") (pin "65") (pinfunction "DRGND_65") (pintype "power_in"))
      (node (ref "IC51") (pin "15") (pinfunction "-VS2_15") (pintype "power_in"))
      (node (ref "IC51") (pin "16") (pinfunction "-VS2_16") (pintype "power_in"))
      (node (ref "IC51") (pin "21") (pinfunction "-VS1_21") (pintype "power_in"))
      (node (ref "IC51") (pin "22") (pinfunction "-VS1_22") (pintype "power_in"))
      (node (ref "IC51") (pin "25") (pinfunction "EPAD(GND)_25") (pintype "passive"))
      (node (ref "R298") (pin "1") (pinfunction "1_1") (pintype "passive"))
      (node (ref "R300") (pin "1") (pinfunction "1_1") (pintype "passive"))
      (node (ref "R302") (pin "1") (pinfunction "1_1") (pintype "passive"))
    )
    (net (code "62") (name "Net-(FR115-Pad1)") (class "Default")
      (node (ref "FR115") (pin "1") (pinfunction "1_1") (pintype "passive"))
      (node (ref "R303") (pin "1") (pinfunction "1_1") (pintype "passive"))
      (node (ref "R304") (pin "1") (pinfunction "1_1") (pintype "passive"))
    )
    (net (code "63") (name "Net-(IC51A-+FB1)") (class "Default")
      (node (ref "IC51") (pin "2") (pinfunction "+FB1_2") (pintype "output"))
      (node (ref "R284") (pin "1") (pinfunction "1_1") (pintype "passive"))
    )
    (net (code "64") (name "Net-(IC51A-+IN1)") (class "Default")
      (node (ref "IC51") (pin "24") (pinfunction "+IN1_24") (pintype "input"))
      (node (ref "R279") (pin "2") (pinfunction "2_2") (pintype "passive"))
      (node (ref "R283") (pin "1") (pinfunction "1_1") (pintype "passive"))
    )
    (net (code "65") (name "Net-(IC51A--FB1)") (class "Default")
      (node (ref "IC51") (pin "23") (pinfunction "-FB1_23") (pintype "output"))
      (node (ref "R279") (pin "1") (pinfunction "1_1") (pintype "passive"))
    )
    (net (code "66") (name "Net-(IC51A--IN1)") (class "Default")
      (node (ref "IC51") (pin "1") (pinfunction "-IN1_1") (pintype "input"))
      (node (ref "R277") (pin "1") (pinfunction "1_1") (pintype "passive"))
      (node (ref "R284") (pin "2") (pinfunction "2_2") (pintype "passive"))
    )
    (net (code "67") (name "Net-(IC51B-+FB2)") (class "Default")
      (node (ref "IC51") (pin "8") (pinfunction "+FB2_8") (pintype "output"))
      (node (ref "R294") (pin "1") (pinfunction "1_1") (pintype "passive"))
    )
    (net (code "68") (name "Net-(IC51B-+IN2)") (class "Default")
      (node (ref "IC51") (pin "6") (pinfunction "+IN2_6") (pintype "input"))
      (node (ref "R289") (pin "2") (pinfunction "2_2") (pintype "passive"))
      (node (ref "R293") (pin "1") (pinfunction "1_1") (pintype "passive"))
    )
    (net (code "69") (name "Net-(IC51B--FB2)") (class "Default")
      (node (ref "IC51") (pin "5") (pinfunction "-FB2_5") (pintype "output"))
      (node (ref "R289") (pin "1") (pinfunction "1_1") (pintype "passive"))
    )
    (net (code "70") (name "Net-(IC51B--IN2)") (class "Default")
      (node (ref "IC51") (pin "7") (pinfunction "-IN2_7") (pintype "input"))
      (node (ref "R288") (pin "1") (pinfunction "1_1") (pintype "passive"))
      (node (ref "R294") (pin "2") (pinfunction "2_2") (pintype "passive"))
    )
    (net (code "71") (name "VCC1P8A") (class "Default")
      (node (ref "FR116") (pin "1") (pinfunction "1_1") (pintype "passive"))
      (node (ref "FR117") (pin "1") (pinfunction "1_1") (pintype "passive"))
    )
    (net (code "72") (name "VCC1P8A_LMS2_BB_ADC1") (class "Default")
      (node (ref "C603") (pin "2") (pinfunction "2_2") (pintype "passive"))
      (node (ref "C604") (pin "2") (pinfunction "2_2") (pintype "passive"))
      (node (ref "C605") (pin "2") (pinfunction "2_2") (pintype "passive"))
      (node (ref "C606") (pin "2") (pinfunction "2_2") (pintype "passive"))
      (node (ref "C607") (pin "2") (pinfunction "2_2") (pintype "passive"))
      (node (ref "C608") (pin "2") (pinfunction "2_2") (pintype "passive"))
      (node (ref "C609") (pin "1") (pinfunction "1_1") (pintype "passive"))
      (node (ref "FR117") (pin "2") (pinfunction "2_2") (pintype "passive"))
      (node (ref "IC50") (pin "16") (pinfunction "AVDD_16") (pintype "power_in"))
      (node (ref "IC50") (pin "22") (pinfunction "AVDD_22") (pintype "power_in"))
      (node (ref "IC50") (pin "33") (pinfunction "AVDD_33") (pintype "power_in"))
      (node (ref "IC50") (pin "34") (pinfunction "AVDD_34") (pintype "power_in"))
    )
    (net (code "73") (name "VCC1P8D_LMS2_BB_ADC1") (class "Default")
      (node (ref "C598") (pin "2") (pinfunction "2_2") (pintype "passive"))
      (node (ref "C599") (pin "2") (pinfunction "2_2") (pintype "passive"))
      (node (ref "C600") (pin "2") (pinfunction "2_2") (pintype "passive"))
      (node (ref "C601") (pin "2") (pinfunction "2_2") (pintype "passive"))
      (node (ref "C602") (pin "1") (pinfunction "1_1") (pintype "passive"))
      (node (ref "FR116") (pin "2") (pinfunction "2_2") (pintype "passive"))
      (node (ref "IC50") (pin "1") (pinfunction "DRVDD_1") (pintype "power_in"))
      (node (ref "IC50") (pin "48") (pinfunction "DRVDD_48") (pintype "power_in"))
      (node (ref "R297") (pin "2") (pinfunction "2_2") (pintype "passive"))
      (node (ref "R299") (pin "2") (pinfunction "2_2") (pintype "passive"))
      (node (ref "R301") (pin "2") (pinfunction "2_2") (pintype "passive"))
    )
    (net (code "74") (name "VCC3P3") (class "Default")
      (node (ref "R303") (pin "2") (pinfunction "2_2") (pintype "passive"))
    )
    (net (code "75") (name "VCC5P0") (class "Default")
      (node (ref "R304") (pin "2") (pinfunction "2_2") (pintype "passive"))
    )
    (net (code "76") (name "VCC_LMS2_BB_ADCDRV1") (class "Default")
      (node (ref "C587") (pin "2") (pinfunction "2_2") (pintype "passive"))
      (node (ref "C588") (pin "1") (pinfunction "1_1") (pintype "passive"))
      (node (ref "C589") (pin "1") (pinfunction "1_1") (pintype "passive"))
      (node (ref "C594") (pin "2") (pinfunction "2_2") (pintype "passive"))
      (node (ref "C595") (pin "1") (pinfunction "1_1") (pintype "passive"))
      (node (ref "C596") (pin "1") (pinfunction "1_1") (pintype "passive"))
      (node (ref "C597") (pin "2") (pinfunction "2_2") (pintype "passive"))
      (node (ref "FR115") (pin "2") (pinfunction "2_2") (pintype "passive"))
      (node (ref "IC51") (pin "10") (pinfunction "+VS2_10") (pintype "power_in"))
      (node (ref "IC51") (pin "3") (pinfunction "+VS1_3") (pintype "power_in"))
      (node (ref "IC51") (pin "4") (pinfunction "+VS1_4") (pintype "power_in"))
      (node (ref "IC51") (pin "9") (pinfunction "+VS2_9") (pintype "power_in"))
      (node (ref "R287") (pin "2") (pinfunction "2_2") (pintype "passive"))
    )
    (net (code "77") (name "unconnected-(FL17-Pad1)") (class "Default")
      (node (ref "FL17") (pin "1") (pintype "passive+no_connect"))
    )
    (net (code "78") (name "unconnected-(IC50C-NC-Pad38)") (class "Default")
      (node (ref "IC50") (pin "38") (pinfunction "NC_38") (pintype "passive+no_connect"))
    )
    (net (code "79") (name "unconnected-(IC50C-NC-Pad39)") (class "Default")
      (node (ref "IC50") (pin "39") (pinfunction "NC_39") (pintype "passive+no_connect"))
    )
    (net (code "80") (name "unconnected-(IC50C-NC-Pad58)") (class "Default")
      (node (ref "IC50") (pin "58") (pinfunction "NC_58") (pintype "passive+no_connect"))
    )
    (net (code "81") (name "unconnected-(IC50C-NC-Pad59)") (class "Default")
      (node (ref "IC50") (pin "59") (pinfunction "NC_59") (pintype "passive+no_connect"))
    )
  )
)
